# S08_DisplayPort.net
KiCad netlist of a schematic drawn in Altium Designer
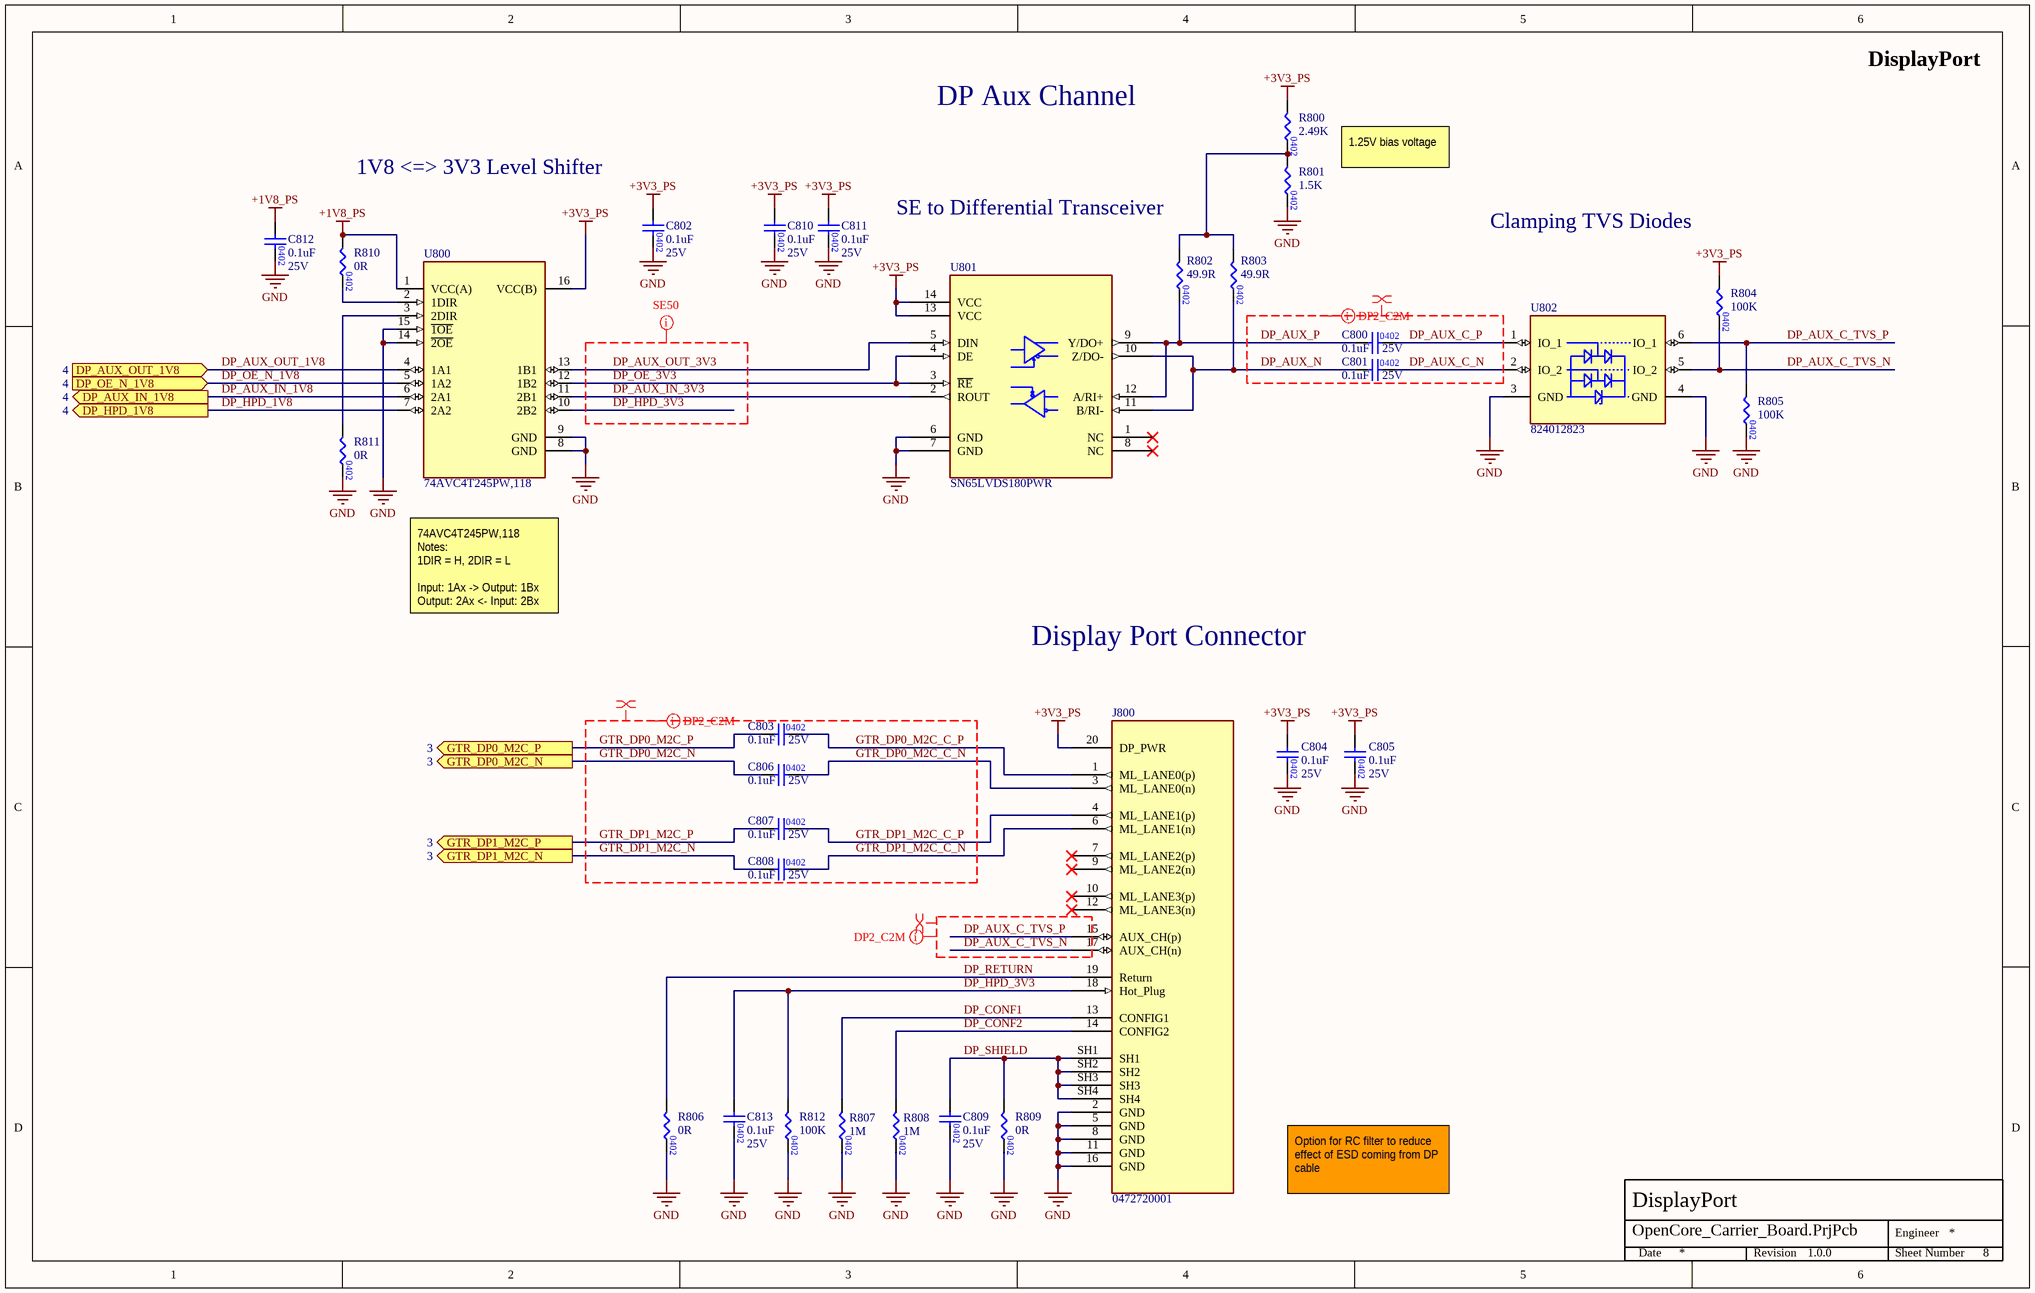
[diagram p0: S08_DisplayPort.SchDoc]

(export (version "E")
  (design (tool "Eeschema 10.0.6"))
  (components
    (comp (ref "C800")
      (value "0.1uF")
      (footprint "CAP0402")
      (description "CAP CER 0.1UF 25V X5R 0402")
      (fields
        (field (name "MANUFACTURER") "Samsung Electro-Mechanics")
        (field (name "TOLERANCE") "10%")
        (field (name "VOLTAGE RATING") "25V")
      )
      (libsource (lib "OpenCore_Sch_Lib") (part "CAP_CL05A104KA5NNNC"))
    )
    (comp (ref "C801")
      (value "0.1uF")
      (footprint "CAP0402")
      (description "CAP CER 0.1UF 25V X5R 0402")
      (fields
        (field (name "MANUFACTURER") "Samsung Electro-Mechanics")
        (field (name "TOLERANCE") "10%")
        (field (name "VOLTAGE RATING") "25V")
      )
      (libsource (lib "OpenCore_Sch_Lib") (part "CAP_CL05A104KA5NNNC"))
    )
    (comp (ref "C802")
      (value "0.1uF")
      (footprint "CAP0402")
      (description "CAP CER 0.1UF 25V X5R 0402")
      (fields
        (field (name "MANUFACTURER") "Samsung Electro-Mechanics")
        (field (name "TOLERANCE") "10%")
        (field (name "VOLTAGE RATING") "25V")
      )
      (libsource (lib "OpenCore_Sch_Lib") (part "CAP_CL05A104KA5NNNC"))
    )
    (comp (ref "C803")
      (value "0.1uF")
      (footprint "CAP0402")
      (description "CAP CER 0.1UF 25V X5R 0402")
      (fields
        (field (name "MANUFACTURER") "Samsung Electro-Mechanics")
        (field (name "TOLERANCE") "10%")
        (field (name "VOLTAGE RATING") "25V")
      )
      (libsource (lib "OpenCore_Sch_Lib") (part "CAP_CL05A104KA5NNNC"))
    )
    (comp (ref "C804")
      (value "0.1uF")
      (footprint "CAP0402")
      (description "CAP CER 0.1UF 25V X5R 0402")
      (fields
        (field (name "MANUFACTURER") "Samsung Electro-Mechanics")
        (field (name "TOLERANCE") "10%")
        (field (name "VOLTAGE RATING") "25V")
      )
      (libsource (lib "OpenCore_Sch_Lib") (part "CAP_CL05A104KA5NNNC"))
    )
    (comp (ref "C805")
      (value "0.1uF")
      (footprint "CAP0402")
      (description "CAP CER 0.1UF 25V X5R 0402")
      (fields
        (field (name "MANUFACTURER") "Samsung Electro-Mechanics")
        (field (name "TOLERANCE") "10%")
        (field (name "VOLTAGE RATING") "25V")
      )
      (libsource (lib "OpenCore_Sch_Lib") (part "CAP_CL05A104KA5NNNC"))
    )
    (comp (ref "C806")
      (value "0.1uF")
      (footprint "CAP0402")
      (description "CAP CER 0.1UF 25V X5R 0402")
      (fields
        (field (name "MANUFACTURER") "Samsung Electro-Mechanics")
        (field (name "TOLERANCE") "10%")
        (field (name "VOLTAGE RATING") "25V")
      )
      (libsource (lib "OpenCore_Sch_Lib") (part "CAP_CL05A104KA5NNNC"))
    )
    (comp (ref "C807")
      (value "0.1uF")
      (footprint "CAP0402")
      (description "CAP CER 0.1UF 25V X5R 0402")
      (fields
        (field (name "MANUFACTURER") "Samsung Electro-Mechanics")
        (field (name "TOLERANCE") "10%")
        (field (name "VOLTAGE RATING") "25V")
      )
      (libsource (lib "OpenCore_Sch_Lib") (part "CAP_CL05A104KA5NNNC"))
    )
    (comp (ref "C808")
      (value "0.1uF")
      (footprint "CAP0402")
      (description "CAP CER 0.1UF 25V X5R 0402")
      (fields
        (field (name "MANUFACTURER") "Samsung Electro-Mechanics")
        (field (name "TOLERANCE") "10%")
        (field (name "VOLTAGE RATING") "25V")
      )
      (libsource (lib "OpenCore_Sch_Lib") (part "CAP_CL05A104KA5NNNC"))
    )
    (comp (ref "C809")
      (value "0.1uF")
      (footprint "CAP0402")
      (description "CAP CER 0.1UF 25V X5R 0402")
      (fields
        (field (name "MANUFACTURER") "Samsung Electro-Mechanics")
        (field (name "TOLERANCE") "10%")
        (field (name "VOLTAGE RATING") "25V")
      )
      (libsource (lib "OpenCore_Sch_Lib") (part "CAP_CL05A104KA5NNNC"))
    )
    (comp (ref "C810")
      (value "0.1uF")
      (footprint "CAP0402")
      (description "CAP CER 0.1UF 25V X5R 0402")
      (fields
        (field (name "MANUFACTURER") "Samsung Electro-Mechanics")
        (field (name "TOLERANCE") "10%")
        (field (name "VOLTAGE RATING") "25V")
      )
      (libsource (lib "OpenCore_Sch_Lib") (part "CAP_CL05A104KA5NNNC"))
    )
    (comp (ref "C811")
      (value "0.1uF")
      (footprint "CAP0402")
      (description "CAP CER 0.1UF 25V X5R 0402")
      (fields
        (field (name "MANUFACTURER") "Samsung Electro-Mechanics")
        (field (name "TOLERANCE") "10%")
        (field (name "VOLTAGE RATING") "25V")
      )
      (libsource (lib "OpenCore_Sch_Lib") (part "CAP_CL05A104KA5NNNC"))
    )
    (comp (ref "C812")
      (value "0.1uF")
      (footprint "CAP0402")
      (description "CAP CER 0.1UF 25V X5R 0402")
      (fields
        (field (name "MANUFACTURER") "Samsung Electro-Mechanics")
        (field (name "TOLERANCE") "10%")
        (field (name "VOLTAGE RATING") "25V")
      )
      (libsource (lib "OpenCore_Sch_Lib") (part "CAP_CL05A104KA5NNNC"))
    )
    (comp (ref "C813")
      (value "0.1uF")
      (footprint "CAP0402")
      (description "CAP CER 0.1UF 25V X5R 0402")
      (fields
        (field (name "MANUFACTURER") "Samsung Electro-Mechanics")
        (field (name "TOLERANCE") "10%")
        (field (name "VOLTAGE RATING") "25V")
      )
      (libsource (lib "OpenCore_Sch_Lib") (part "CAP_CL05A104KA5NNNC"))
    )
    (comp (ref "J800")
      (value "0472720001")
      (footprint "0472720001")
      (description "CONN RCPT DISPLAYPORT 20P SMD RA")
      (libsource (lib "OpenCore_Sch_Lib") (part "0472720001"))
    )
    (comp (ref "R800")
      (value "RES_0402")
      (footprint "RES0402")
      (description "RES 2.49K OHM 1% 1/16W 0402")
      (fields
        (field (name "MANUFACTURER") "YAGEO")
        (field (name "MANUFACTURER PART NUMBER") "RC0402FR-072K49L")
        (field (name "RESISTANCE") "2.49K")
      )
      (libsource (lib "OpenCore_Sch_Lib") (part ".RES_RC0402FR-072K49L"))
    )
    (comp (ref "R801")
      (value "RES_0402")
      (footprint "RES0402")
      (description "RES 1.5K OHM 1% 1/16W 0402")
      (fields
        (field (name "MANUFACTURER") "YAGEO")
        (field (name "MANUFACTURER PART NUMBER") "RC0402FR-071K5L")
        (field (name "RESISTANCE") "1.5K")
      )
      (libsource (lib "OpenCore_Sch_Lib") (part ".RES_RC0402FR-071K5L"))
    )
    (comp (ref "R802")
      (value "RES_0402")
      (footprint "RES0402")
      (description "RES 49.9 OHM 1% 1/16W 0402")
      (fields
        (field (name "MANUFACTURER") "YAGEO")
        (field (name "MANUFACTURER PART NUMBER") "RC0402FR-0749R9L")
        (field (name "RESISTANCE") "49.9R")
      )
      (libsource (lib "OpenCore_Sch_Lib") (part ".RES_RC0402FR-0749R9L"))
    )
    (comp (ref "R803")
      (value "RES_0402")
      (footprint "RES0402")
      (description "RES 49.9 OHM 1% 1/16W 0402")
      (fields
        (field (name "MANUFACTURER") "YAGEO")
        (field (name "MANUFACTURER PART NUMBER") "RC0402FR-0749R9L")
        (field (name "RESISTANCE") "49.9R")
      )
      (libsource (lib "OpenCore_Sch_Lib") (part ".RES_RC0402FR-0749R9L"))
    )
    (comp (ref "R804")
      (value "RES_0402")
      (footprint "RES0402")
      (description "RES 100K OHM 1% 1/16W 0402")
      (fields
        (field (name "MANUFACTURER") "YAGEO")
        (field (name "MANUFACTURER PART NUMBER") "RC0402FR-07100KL")
        (field (name "RESISTANCE") "100K")
      )
      (libsource (lib "OpenCore_Sch_Lib") (part ".RES_RC0402FR-07100KL"))
    )
    (comp (ref "R805")
      (value "RES_0402")
      (footprint "RES0402")
      (description "RES 100K OHM 1% 1/16W 0402")
      (fields
        (field (name "MANUFACTURER") "YAGEO")
        (field (name "MANUFACTURER PART NUMBER") "RC0402FR-07100KL")
        (field (name "RESISTANCE") "100K")
      )
      (libsource (lib "OpenCore_Sch_Lib") (part ".RES_RC0402FR-07100KL"))
    )
    (comp (ref "R806")
      (value "RES_0402")
      (footprint "RES0402")
      (description "RES 0 OHM JUMPER 1/16W 0402")
      (fields
        (field (name "MANUFACTURER") "YAGEO")
        (field (name "MANUFACTURER PART NUMBER") "RC0402JR-070RL")
        (field (name "RESISTANCE") "0R")
      )
      (libsource (lib "OpenCore_Sch_Lib") (part ".RES_RC0402JR-070RL"))
    )
    (comp (ref "R807")
      (value "RES_0402")
      (footprint "RES0402")
      (description "RES 1M OHM 1% 1/16W 0402")
      (fields
        (field (name "MANUFACTURER") "YAGEO")
        (field (name "MANUFACTURER PART NUMBER") "RC0402FR-071ML")
        (field (name "RESISTANCE") "1M")
      )
      (libsource (lib "OpenCore_Sch_Lib") (part ".RES_RC0402FR-071ML"))
    )
    (comp (ref "R808")
      (value "RES_0402")
      (footprint "RES0402")
      (description "RES 1M OHM 1% 1/16W 0402")
      (fields
        (field (name "MANUFACTURER") "YAGEO")
        (field (name "MANUFACTURER PART NUMBER") "RC0402FR-071ML")
        (field (name "RESISTANCE") "1M")
      )
      (libsource (lib "OpenCore_Sch_Lib") (part ".RES_RC0402FR-071ML"))
    )
    (comp (ref "R809")
      (value "RES_0402")
      (footprint "RES0402")
      (description "RES 0 OHM JUMPER 1/16W 0402")
      (fields
        (field (name "MANUFACTURER") "YAGEO")
        (field (name "MANUFACTURER PART NUMBER") "RC0402JR-070RL")
        (field (name "RESISTANCE") "0R")
      )
      (libsource (lib "OpenCore_Sch_Lib") (part ".RES_RC0402JR-070RL"))
    )
    (comp (ref "R810")
      (value "RES_0402")
      (footprint "RES0402")
      (description "RES 0 OHM JUMPER 1/16W 0402")
      (fields
        (field (name "MANUFACTURER") "YAGEO")
        (field (name "MANUFACTURER PART NUMBER") "RC0402JR-070RL")
        (field (name "RESISTANCE") "0R")
      )
      (libsource (lib "OpenCore_Sch_Lib") (part ".RES_RC0402JR-070RL"))
    )
    (comp (ref "R811")
      (value "RES_0402")
      (footprint "RES0402")
      (description "RES 0 OHM JUMPER 1/16W 0402")
      (fields
        (field (name "MANUFACTURER") "YAGEO")
        (field (name "MANUFACTURER PART NUMBER") "RC0402JR-070RL")
        (field (name "RESISTANCE") "0R")
      )
      (libsource (lib "OpenCore_Sch_Lib") (part ".RES_RC0402JR-070RL"))
    )
    (comp (ref "R812")
      (value "RES_0402")
      (footprint "RES0402")
      (description "RES 100K OHM 1% 1/16W 0402")
      (fields
        (field (name "MANUFACTURER") "YAGEO")
        (field (name "MANUFACTURER PART NUMBER") "RC0402FR-07100KL")
        (field (name "RESISTANCE") "100K")
      )
      (libsource (lib "OpenCore_Sch_Lib") (part ".RES_RC0402FR-07100KL"))
    )
    (comp (ref "U800")
      (value "74AVC4T245PW,118")
      (footprint "SOP65P640X110-16N")
      (description "IC TRANSLATION TXRX 3.6V 16TSSOP")
      (fields (field (name "MOUSER PART NUMBER") "771-74AVC4T245PW118"))
      (libsource (lib "OpenCore_Sch_Lib") (part "74AVC4T245PW,118"))
    )
    (comp (ref "U801")
      (value "SN65LVDS180PWR")
      (footprint "TI_TSSOP14_PW")
      (description "IC TRANSCEIVER FULL 1/1 14TSSOP")
      (libsource (lib "OpenCore_Sch_Lib") (part "SN65LVDS180PWR"))
    )
    (comp (ref "U802")
      (value "824012823")
      (footprint "824012823")
      (description "TVS DIODE 3.3VWM 13VC DFN1210-6")
      (fields (field (name "MOUSER PART NUMBER") "710-824012823"))
      (libsource (lib "OpenCore_Sch_Lib") (part "824012823"))
    )
  )
  (nets
    (net (code "1") (name "+1V8_PS") (class "Default")
      (node (ref "C812") (pin "1") (pinfunction "1_1") (pintype "passive"))
      (node (ref "R810") (pin "1") (pinfunction "1_1") (pintype "passive"))
      (node (ref "U800") (pin "1") (pinfunction "VCC(A)_1") (pintype "power_in"))
    )
    (net (code "2") (name "+3V3_PS") (class "Default")
      (node (ref "C802") (pin "1") (pinfunction "1_1") (pintype "passive"))
      (node (ref "C804") (pin "1") (pinfunction "1_1") (pintype "passive"))
      (node (ref "C805") (pin "1") (pinfunction "1_1") (pintype "passive"))
      (node (ref "C810") (pin "1") (pinfunction "1_1") (pintype "passive"))
      (node (ref "C811") (pin "1") (pinfunction "1_1") (pintype "passive"))
      (node (ref "J800") (pin "20") (pinfunction "DP_PWR_20") (pintype "power_in"))
      (node (ref "R800") (pin "1") (pinfunction "1_1") (pintype "passive"))
      (node (ref "R804") (pin "1") (pinfunction "1_1") (pintype "passive"))
      (node (ref "U800") (pin "16") (pinfunction "VCC(B)_16") (pintype "power_in"))
      (node (ref "U801") (pin "13") (pinfunction "VCC_13") (pintype "power_in"))
      (node (ref "U801") (pin "14") (pinfunction "VCC_14") (pintype "power_in"))
    )
    (net (code "3") (name "/DP_AUX_C_N") (class "Default")
      (node (ref "C801") (pin "2") (pinfunction "2_2") (pintype "passive"))
      (node (ref "U802") (pin "2") (pinfunction "IO_2_2") (pintype "bidirectional"))
    )
    (net (code "4") (name "/DP_AUX_C_P") (class "Default")
      (node (ref "C800") (pin "2") (pinfunction "2_2") (pintype "passive"))
      (node (ref "U802") (pin "1") (pinfunction "IO_1_1") (pintype "bidirectional"))
    )
    (net (code "5") (name "/DP_AUX_C_TVS_N") (class "Default")
      (node (ref "J800") (pin "17") (pinfunction "AUX_CH(n)_17") (pintype "bidirectional"))
      (node (ref "R804") (pin "2") (pinfunction "2_2") (pintype "passive"))
      (node (ref "U802") (pin "5") (pinfunction "IO_2_5") (pintype "bidirectional"))
    )
    (net (code "6") (name "/DP_AUX_C_TVS_P") (class "Default")
      (node (ref "J800") (pin "15") (pinfunction "AUX_CH(p)_15") (pintype "bidirectional"))
      (node (ref "R805") (pin "1") (pinfunction "1_1") (pintype "passive"))
      (node (ref "U802") (pin "6") (pinfunction "IO_1_6") (pintype "bidirectional"))
    )
    (net (code "7") (name "/DP_AUX_IN_1V8") (class "Default")
      (node (ref "U800") (pin "6") (pinfunction "2A1_6") (pintype "bidirectional"))
    )
    (net (code "8") (name "/DP_AUX_IN_3V3") (class "Default")
      (node (ref "U800") (pin "11") (pinfunction "2B1_11") (pintype "bidirectional"))
      (node (ref "U801") (pin "2") (pinfunction "ROUT_2") (pintype "output"))
    )
    (net (code "9") (name "/DP_AUX_N") (class "Default")
      (node (ref "C801") (pin "1") (pinfunction "1_1") (pintype "passive"))
      (node (ref "R803") (pin "2") (pinfunction "2_2") (pintype "passive"))
      (node (ref "U801") (pin "10") (pinfunction "Z/DO-_10") (pintype "output"))
      (node (ref "U801") (pin "11") (pinfunction "B/RI-_11") (pintype "input"))
    )
    (net (code "10") (name "/DP_AUX_OUT_1V8") (class "Default")
      (node (ref "U800") (pin "4") (pinfunction "1A1_4") (pintype "bidirectional"))
    )
    (net (code "11") (name "/DP_AUX_OUT_3V3") (class "Default")
      (node (ref "U800") (pin "13") (pinfunction "1B1_13") (pintype "bidirectional"))
      (node (ref "U801") (pin "5") (pinfunction "DIN_5") (pintype "input"))
    )
    (net (code "12") (name "/DP_AUX_P") (class "Default")
      (node (ref "C800") (pin "1") (pinfunction "1_1") (pintype "passive"))
      (node (ref "R802") (pin "2") (pinfunction "2_2") (pintype "passive"))
      (node (ref "U801") (pin "12") (pinfunction "A/RI+_12") (pintype "input"))
      (node (ref "U801") (pin "9") (pinfunction "Y/DO+_9") (pintype "output"))
    )
    (net (code "13") (name "/DP_CONF1") (class "Default")
      (node (ref "J800") (pin "13") (pinfunction "CONFIG1_13") (pintype "passive"))
      (node (ref "R807") (pin "1") (pinfunction "1_1") (pintype "passive"))
    )
    (net (code "14") (name "/DP_CONF2") (class "Default")
      (node (ref "J800") (pin "14") (pinfunction "CONFIG2_14") (pintype "passive"))
      (node (ref "R808") (pin "1") (pinfunction "1_1") (pintype "passive"))
    )
    (net (code "15") (name "/DP_HPD_1V8") (class "Default")
      (node (ref "U800") (pin "7") (pinfunction "2A2_7") (pintype "bidirectional"))
    )
    (net (code "16") (name "/DP_HPD_3V3") (class "Default")
      (node (ref "C813") (pin "1") (pinfunction "1_1") (pintype "passive"))
      (node (ref "J800") (pin "18") (pinfunction "Hot_Plug_18") (pintype "input"))
      (node (ref "R812") (pin "1") (pinfunction "1_1") (pintype "passive"))
      (node (ref "U800") (pin "10") (pinfunction "2B2_10") (pintype "bidirectional"))
    )
    (net (code "17") (name "/DP_OE_3V3") (class "Default")
      (node (ref "U800") (pin "12") (pinfunction "1B2_12") (pintype "bidirectional"))
      (node (ref "U801") (pin "3") (pinfunction "~{RE}_3") (pintype "input"))
      (node (ref "U801") (pin "4") (pinfunction "DE_4") (pintype "input"))
    )
    (net (code "18") (name "/DP_OE_N_1V8") (class "Default")
      (node (ref "U800") (pin "5") (pinfunction "1A2_5") (pintype "bidirectional"))
    )
    (net (code "19") (name "/DP_RETURN") (class "Default")
      (node (ref "J800") (pin "19") (pinfunction "Return_19") (pintype "power_in"))
      (node (ref "R806") (pin "1") (pinfunction "1_1") (pintype "passive"))
    )
    (net (code "20") (name "/DP_SHIELD") (class "Default")
      (node (ref "C809") (pin "1") (pinfunction "1_1") (pintype "passive"))
      (node (ref "J800") (pin "SH1") (pinfunction "SH1_SH1") (pintype "passive"))
      (node (ref "J800") (pin "SH2") (pinfunction "SH2_SH2") (pintype "passive"))
      (node (ref "J800") (pin "SH3") (pinfunction "SH3_SH3") (pintype "passive"))
      (node (ref "J800") (pin "SH4") (pinfunction "SH4_SH4") (pintype "passive"))
      (node (ref "R809") (pin "1") (pinfunction "1_1") (pintype "passive"))
    )
    (net (code "21") (name "/GTR_DP0_M2C_C_N") (class "Default")
      (node (ref "C806") (pin "2") (pinfunction "2_2") (pintype "passive"))
      (node (ref "J800") (pin "3") (pinfunction "ML_LANE0(n)_3") (pintype "output"))
    )
    (net (code "22") (name "/GTR_DP0_M2C_C_P") (class "Default")
      (node (ref "C803") (pin "2") (pinfunction "2_2") (pintype "passive"))
      (node (ref "J800") (pin "1") (pinfunction "ML_LANE0(p)_1") (pintype "output"))
    )
    (net (code "23") (name "/GTR_DP0_M2C_N") (class "Default")
      (node (ref "C806") (pin "1") (pinfunction "1_1") (pintype "passive"))
    )
    (net (code "24") (name "/GTR_DP0_M2C_P") (class "Default")
      (node (ref "C803") (pin "1") (pinfunction "1_1") (pintype "passive"))
    )
    (net (code "25") (name "/GTR_DP1_M2C_C_N") (class "Default")
      (node (ref "C808") (pin "2") (pinfunction "2_2") (pintype "passive"))
      (node (ref "J800") (pin "6") (pinfunction "ML_LANE1(n)_6") (pintype "output"))
    )
    (net (code "26") (name "/GTR_DP1_M2C_C_P") (class "Default")
      (node (ref "C807") (pin "2") (pinfunction "2_2") (pintype "passive"))
      (node (ref "J800") (pin "4") (pinfunction "ML_LANE1(p)_4") (pintype "output"))
    )
    (net (code "27") (name "/GTR_DP1_M2C_N") (class "Default")
      (node (ref "C808") (pin "1") (pinfunction "1_1") (pintype "passive"))
    )
    (net (code "28") (name "/GTR_DP1_M2C_P") (class "Default")
      (node (ref "C807") (pin "1") (pinfunction "1_1") (pintype "passive"))
    )
    (net (code "29") (name "GND") (class "Default")
      (node (ref "C802") (pin "2") (pinfunction "2_2") (pintype "passive"))
      (node (ref "C804") (pin "2") (pinfunction "2_2") (pintype "passive"))
      (node (ref "C805") (pin "2") (pinfunction "2_2") (pintype "passive"))
      (node (ref "C809") (pin "2") (pinfunction "2_2") (pintype "passive"))
      (node (ref "C810") (pin "2") (pinfunction "2_2") (pintype "passive"))
      (node (ref "C811") (pin "2") (pinfunction "2_2") (pintype "passive"))
      (node (ref "C812") (pin "2") (pinfunction "2_2") (pintype "passive"))
      (node (ref "C813") (pin "2") (pinfunction "2_2") (pintype "passive"))
      (node (ref "J800") (pin "11") (pinfunction "GND_11") (pintype "power_in"))
      (node (ref "J800") (pin "16") (pinfunction "GND_16") (pintype "power_in"))
      (node (ref "J800") (pin "2") (pinfunction "GND_2") (pintype "power_in"))
      (node (ref "J800") (pin "5") (pinfunction "GND_5") (pintype "power_in"))
      (node (ref "J800") (pin "8") (pinfunction "GND_8") (pintype "power_in"))
      (node (ref "R801") (pin "2") (pinfunction "2_2") (pintype "passive"))
      (node (ref "R805") (pin "2") (pinfunction "2_2") (pintype "passive"))
      (node (ref "R806") (pin "2") (pinfunction "2_2") (pintype "passive"))
      (node (ref "R807") (pin "2") (pinfunction "2_2") (pintype "passive"))
      (node (ref "R808") (pin "2") (pinfunction "2_2") (pintype "passive"))
      (node (ref "R809") (pin "2") (pinfunction "2_2") (pintype "passive"))
      (node (ref "R811") (pin "2") (pinfunction "2_2") (pintype "passive"))
      (node (ref "R812") (pin "2") (pinfunction "2_2") (pintype "passive"))
      (node (ref "U800") (pin "14") (pinfunction "~{2OE}_14") (pintype "input"))
      (node (ref "U800") (pin "15") (pinfunction "~{1OE}_15") (pintype "input"))
      (node (ref "U800") (pin "8") (pinfunction "GND_8") (pintype "power_in"))
      (node (ref "U800") (pin "9") (pinfunction "GND_9") (pintype "power_in"))
      (node (ref "U801") (pin "6") (pinfunction "GND_6") (pintype "power_in"))
      (node (ref "U801") (pin "7") (pinfunction "GND_7") (pintype "power_in"))
      (node (ref "U802") (pin "3") (pinfunction "GND_3") (pintype "power_in"))
      (node (ref "U802") (pin "4") (pinfunction "GND_4") (pintype "power_in"))
    )
    (net (code "30") (name "Net-(R800-Pad2)") (class "Default")
      (node (ref "R800") (pin "2") (pinfunction "2_2") (pintype "passive"))
      (node (ref "R801") (pin "1") (pinfunction "1_1") (pintype "passive"))
      (node (ref "R802") (pin "1") (pinfunction "1_1") (pintype "passive"))
      (node (ref "R803") (pin "1") (pinfunction "1_1") (pintype "passive"))
    )
    (net (code "31") (name "Net-(U800-1DIR)") (class "Default")
      (node (ref "R810") (pin "2") (pinfunction "2_2") (pintype "passive"))
      (node (ref "U800") (pin "2") (pinfunction "1DIR_2") (pintype "input"))
    )
    (net (code "32") (name "Net-(U800-2DIR)") (class "Default")
      (node (ref "R811") (pin "1") (pinfunction "1_1") (pintype "passive"))
      (node (ref "U800") (pin "3") (pinfunction "2DIR_3") (pintype "input"))
    )
    (net (code "33") (name "unconnected-(J800-ML_LANE2(n)-Pad9)") (class "Default")
      (node (ref "J800") (pin "9") (pinfunction "ML_LANE2(n)_9") (pintype "output+no_connect"))
    )
    (net (code "34") (name "unconnected-(J800-ML_LANE2(p)-Pad7)") (class "Default")
      (node (ref "J800") (pin "7") (pinfunction "ML_LANE2(p)_7") (pintype "output+no_connect"))
    )
    (net (code "35") (name "unconnected-(J800-ML_LANE3(n)-Pad12)") (class "Default")
      (node (ref "J800") (pin "12") (pinfunction "ML_LANE3(n)_12") (pintype "output+no_connect"))
    )
    (net (code "36") (name "unconnected-(J800-ML_LANE3(p)-Pad10)") (class "Default")
      (node (ref "J800") (pin "10") (pinfunction "ML_LANE3(p)_10") (pintype "output+no_connect"))
    )
    (net (code "37") (name "unconnected-(U801-NC-Pad1)") (class "Default")
      (node (ref "U801") (pin "1") (pinfunction "NC_1") (pintype "passive+no_connect"))
    )
    (net (code "38") (name "unconnected-(U801-NC-Pad8)") (class "Default")
      (node (ref "U801") (pin "8") (pinfunction "NC_8") (pintype "passive+no_connect"))
    )
  )
)
